# PowerSupply.net
KiCad netlist of a schematic drawn in Altium Designer
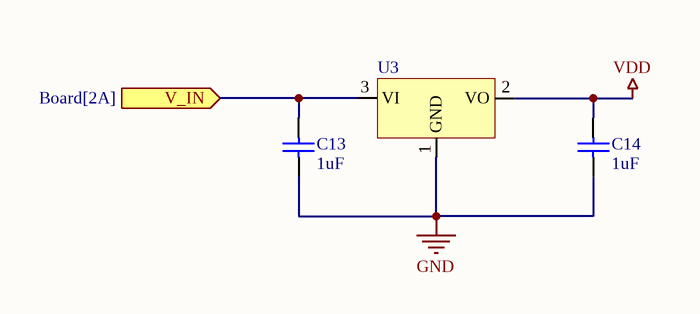
[diagram p0: PowerSupply.SchDoc]

(export (version "E")
  (design (tool "Eeschema 10.0.6"))
  (components
    (comp (ref "C13")
      (value "1uF")
      (footprint "CAP_0402")
      (fields (field (name "MANUFACTURER") "Murata") (field (name "PART NUMBER") "GRM155R71E103KA01D"))
      (libsource (lib "schematics") (part "Capacitor"))
    )
    (comp (ref "C14")
      (value "1uF")
      (footprint "CAP_0402")
      (fields (field (name "MANUFACTURER") "Murata") (field (name "PART NUMBER") "GRM155R71E103KA01D"))
      (libsource (lib "schematics") (part "Capacitor"))
    )
    (comp (ref "U3")
      (value "LDO-Voltage-Regulator-3Pin")
      (footprint "SOT95P237X112-3N")
      (libsource (lib "schematics") (part "LDO-Voltage-Regulator-3Pin"))
    )
  )
  (nets
    (net (code "1") (name "/V_IN") (class "Default")
      (node (ref "C13") (pin "2") (pinfunction "2_2") (pintype "passive"))
      (node (ref "U3") (pin "3") (pinfunction "VI_3") (pintype "passive"))
    )
    (net (code "2") (name "GND") (class "Default")
      (node (ref "C13") (pin "1") (pinfunction "1_1") (pintype "passive"))
      (node (ref "C14") (pin "1") (pinfunction "1_1") (pintype "passive"))
      (node (ref "U3") (pin "1") (pinfunction "GND_1") (pintype "passive"))
    )
    (net (code "3") (name "VDD") (class "Default")
      (node (ref "C14") (pin "2") (pinfunction "2_2") (pintype "passive"))
      (node (ref "U3") (pin "2") (pinfunction "VO_2") (pintype "passive"))
    )
  )
)
